# ATmega324PB_Xplained_Pro_EDBG.net
KiCad netlist of a schematic drawn in Altium Designer
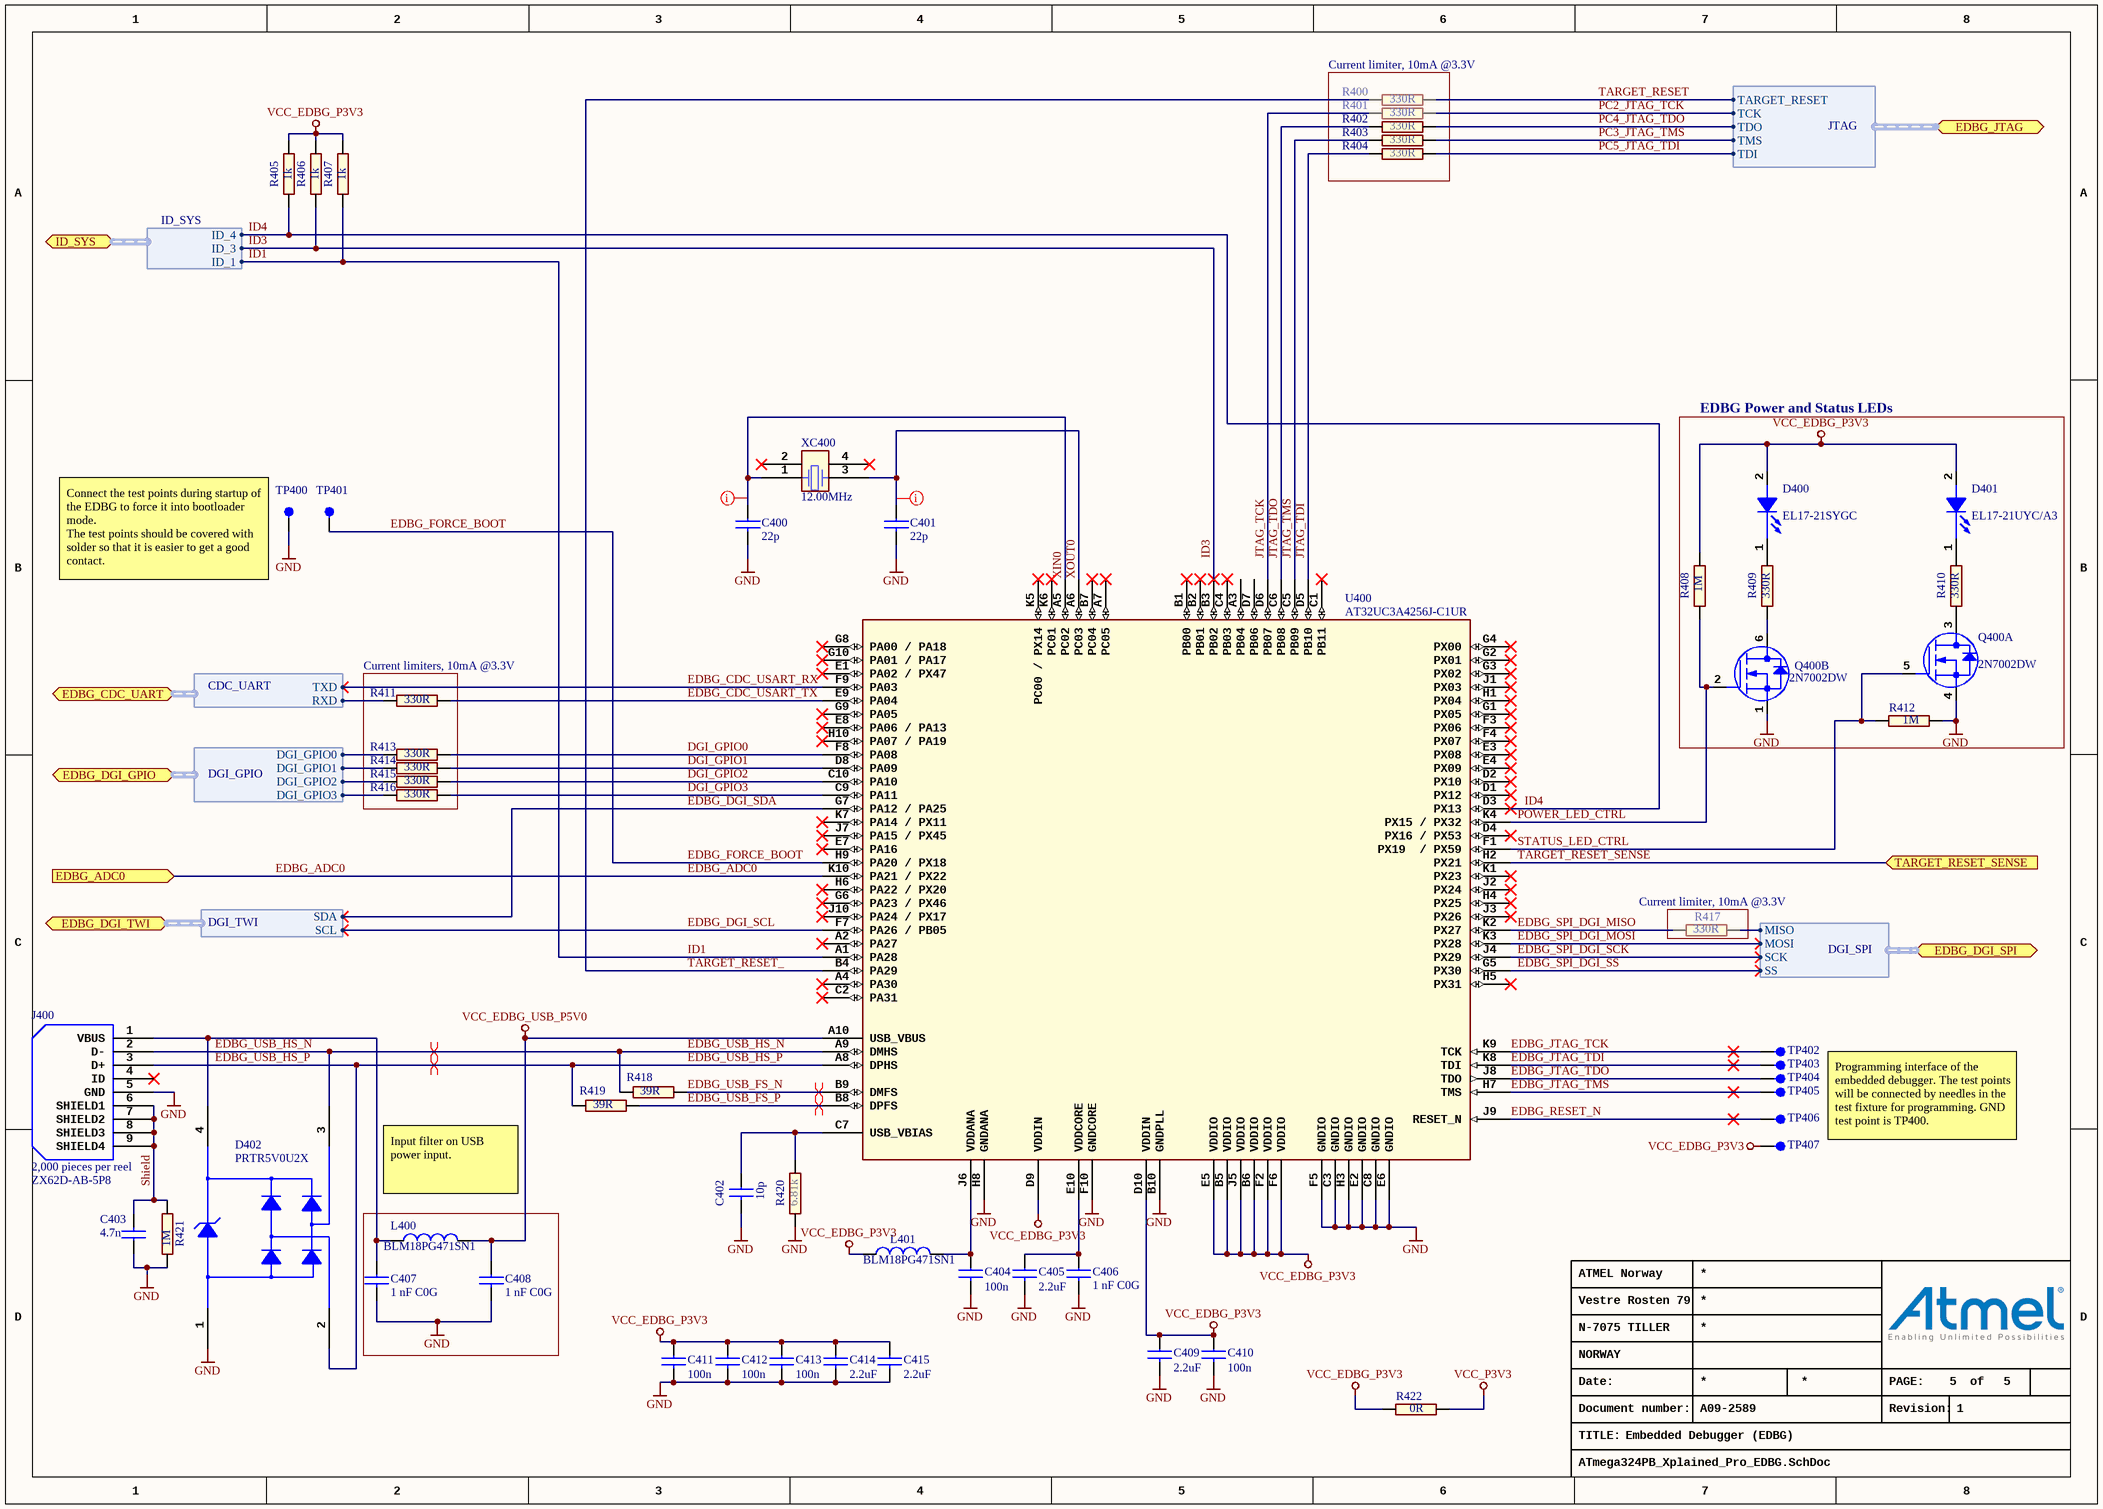
[diagram p0: ATmega324PB_Xplained_Pro_EDBG.SchDoc]

(export (version "E")
  (design (tool "Eeschema 10.0.6"))
  (components
    (comp (ref "C400")
      (value "22p")
      (footprint "AP1-00053")
      (description "Ceramic capacitor, SMD 0402, NP0, 50V, +/-5%")
      (fields (field (name "TOLERANCE") "50V, +/-5%"))
      (libsource (lib "AltiumDbLib") (part "CAP-NONPOL"))
    )
    (comp (ref "C401")
      (value "22p")
      (footprint "AP1-00053")
      (description "Ceramic capacitor, SMD 0402, NP0, 50V, +/-5%")
      (fields (field (name "TOLERANCE") "50V, +/-5%"))
      (libsource (lib "AltiumDbLib") (part "CAP-NONPOL"))
    )
    (comp (ref "C402")
      (value "10p")
      (footprint "AP1-00053")
      (description "Ceramic capacitor, SMD 0402, NP0, 50V, +/-5%")
      (fields (field (name "TOLERANCE") "50V, +/-5%"))
      (libsource (lib "AltiumDbLib") (part "CAP-NONPOL"))
    )
    (comp (ref "C403")
      (value "4.7n")
      (footprint "AP1-00053")
      (description "Ceramic capacitor, SMD 0402, X7R, 25V, +/-10%")
      (fields (field (name "TOLERANCE") "25V, +/-10%"))
      (libsource (lib "AltiumDbLib") (part "CAP-NONPOL"))
    )
    (comp (ref "C404")
      (value "100n")
      (footprint "AP1-00053")
      (description "Ceramic capacitor, SMD 0402, X7R, 16V, +/-10%")
      (fields (field (name "TOLERANCE") "16V, +/-10%") (field (name "MANUFACTURER") "Kemet"))
      (libsource (lib "AltiumDbLib") (part "CAP-NONPOL"))
    )
    (comp (ref "C405")
      (value "2.2uF")
      (footprint "AP1-00053")
      (description "Ceramic capacitor, SMD 0402, X5R, 6.3V, +/-20%")
      (fields (field (name "TOLERANCE") "Â±20%") (field (name "MANUFACTURER") "Kemet"))
      (libsource (lib "AltiumDbLib") (part "CAP-NONPOL"))
    )
    (comp (ref "C406")
      (value "1 nF C0G")
      (footprint "AP1-00053")
      (description "Ceramic capacitor, SMD 0402, C0G, 50V, +/-5%")
      (fields (field (name "TOLERANCE") "5%") (field (name "MANUFACTURER") "Murata"))
      (libsource (lib "AltiumDbLib") (part "CAP-NONPOL"))
    )
    (comp (ref "C407")
      (value "1 nF C0G")
      (footprint "AP1-00053")
      (description "Ceramic capacitor, SMD 0402, C0G, 50V, +/-5%")
      (fields (field (name "TOLERANCE") "5%") (field (name "MANUFACTURER") "Murata"))
      (libsource (lib "AltiumDbLib") (part "CAP-NONPOL"))
    )
    (comp (ref "C408")
      (value "1 nF C0G")
      (footprint "AP1-00053")
      (description "Ceramic capacitor, SMD 0402, C0G, 50V, +/-5%")
      (fields (field (name "TOLERANCE") "5%") (field (name "MANUFACTURER") "Murata"))
      (libsource (lib "AltiumDbLib") (part "CAP-NONPOL"))
    )
    (comp (ref "C409")
      (value "2.2uF")
      (footprint "AP1-00053")
      (description "Ceramic capacitor, SMD 0402, X5R, 6.3V, +/-20%")
      (fields (field (name "TOLERANCE") "Â±20%") (field (name "MANUFACTURER") "Kemet"))
      (libsource (lib "AltiumDbLib") (part "CAP-NONPOL"))
    )
    (comp (ref "C410")
      (value "100n")
      (footprint "AP1-00053")
      (description "Ceramic capacitor, SMD 0402, X7R, 16V, +/-10%")
      (fields (field (name "TOLERANCE") "16V, +/-10%") (field (name "MANUFACTURER") "Kemet"))
      (libsource (lib "AltiumDbLib") (part "CAP-NONPOL"))
    )
    (comp (ref "C411")
      (value "100n")
      (footprint "AP1-00053")
      (description "Ceramic capacitor, SMD 0402, X7R, 16V, +/-10%")
      (fields (field (name "TOLERANCE") "16V, +/-10%") (field (name "MANUFACTURER") "Kemet"))
      (libsource (lib "AltiumDbLib") (part "CAP-NONPOL"))
    )
    (comp (ref "C412")
      (value "100n")
      (footprint "AP1-00053")
      (description "Ceramic capacitor, SMD 0402, X7R, 16V, +/-10%")
      (fields (field (name "TOLERANCE") "16V, +/-10%") (field (name "MANUFACTURER") "Kemet"))
      (libsource (lib "AltiumDbLib") (part "CAP-NONPOL"))
    )
    (comp (ref "C413")
      (value "100n")
      (footprint "AP1-00053")
      (description "Ceramic capacitor, SMD 0402, X7R, 16V, +/-10%")
      (fields (field (name "TOLERANCE") "16V, +/-10%") (field (name "MANUFACTURER") "Kemet"))
      (libsource (lib "AltiumDbLib") (part "CAP-NONPOL"))
    )
    (comp (ref "C414")
      (value "2.2uF")
      (footprint "AP1-00053")
      (description "Ceramic capacitor, SMD 0402, X5R, 6.3V, +/-20%")
      (fields (field (name "TOLERANCE") "Â±20%") (field (name "MANUFACTURER") "Kemet"))
      (libsource (lib "AltiumDbLib") (part "CAP-NONPOL"))
    )
    (comp (ref "C415")
      (value "2.2uF")
      (footprint "AP1-00053")
      (description "Ceramic capacitor, SMD 0402, X5R, 6.3V, +/-20%")
      (fields (field (name "TOLERANCE") "Â±20%") (field (name "MANUFACTURER") "Kemet"))
      (libsource (lib "AltiumDbLib") (part "CAP-NONPOL"))
    )
    (comp (ref "D400")
      (value "EL17-21SYGC")
      (footprint "AP4-00013")
      (description "LED, Green, Wave length=575nm, SMD 0805, ±70°")
      (fields (field (name "MANUFACTURER") "Everlight"))
      (libsource (lib "AltiumDbLib") (part "LED_12"))
    )
    (comp (ref "D401")
      (value "EL17-21UYC/A3")
      (footprint "AP4-00013")
      (description "LED, Yellow, Wave length=591nm, SMD 0805, ±70°")
      (fields (field (name "MANUFACTURER") "Everlight") (field (name "MPN") "17-21UYC/S530-A3/TR8"))
      (libsource (lib "AltiumDbLib") (part "LED_12"))
    )
    (comp (ref "D402")
      (value "PRTR5V0U2X")
      (footprint "AP4-00001")
      (description "Double rail-to-rail USB ESD protection diode")
      (fields
        (field (name "MANUFACTURER") "NXP")
        (field (name "Comment") "Changed manufacturer from Philips to NXP.")
      )
      (libsource (lib "AltiumDbLib") (part "PRTR5V0U2X"))
    )
    (comp (ref "J400")
      (value "2,000 pieces per reel")
      (footprint "AP8-00852")
      (description "Micro USB AB Connector, Standard SMT + DIP")
      (fields
        (field (name "ALTIUM_VALUE") "ZX62D-AB-5P8")
        (field (name "MANUFACTURER") "HIROSE")
        (field (name "MPN") "ZX62D-AB-5P8")
      )
      (libsource (lib "AltiumDbLib") (part "USB_AB"))
    )
    (comp (ref "L400")
      (value "BLM18PG471SN1")
      (footprint "AP3-00005")
      (description "SMD RF inductor 0603. Z=470Ohm (@100MHz), Max R(dc)=0.65Ohm, Max current=1A")
      (fields (field (name "TOLERANCE") "±25%") (field (name "MANUFACTURER") "Murata"))
      (libsource (lib "AltiumDbLib") (part "INDUCTOR"))
    )
    (comp (ref "L401")
      (value "BLM18PG471SN1")
      (footprint "AP3-00005")
      (description "SMD RF inductor 0603. Z=470Ohm (@100MHz), Max R(dc)=0.65Ohm, Max current=1A")
      (fields (field (name "TOLERANCE") "±25%") (field (name "MANUFACTURER") "Murata"))
      (libsource (lib "AltiumDbLib") (part "INDUCTOR"))
    )
    (comp (ref "Q400")
      (value "2N7002DW")
      (footprint "AP5-00001")
      (description "Dual N-Channel MOSFET, 60V, 115mA cont,RDS(ON) < 7.5 Ohm @50mA@5V, SOT-363")
      (fields
        (field (name "MANUFACTURER") "Fairchild")
        (field (name "Comment") "Same as 2N7002 but with two MOSFETs in one package")
      )
      (libsource (lib "AltiumDbLib") (part "MOSFET_DUAL_N_S2G2D1S1G1D2"))
    )
    (comp (ref "R400")
      (value "330R")
      (footprint "AP2-00000")
      (description "Thick film resistor, SMD 0402, 1/16W, 1%")
      (fields (field (name "TOLERANCE") "1 %"))
      (libsource (lib "") (part "R2_1"))
    )
    (comp (ref "R401")
      (value "330R")
      (footprint "AP2-00000")
      (description "Thick film resistor, SMD 0402, 1/16W, 1%")
      (fields (field (name "TOLERANCE") "1 %"))
      (libsource (lib "") (part "R2_1"))
    )
    (comp (ref "R402")
      (value "330R")
      (footprint "AP2-00000")
      (description "Thick film resistor, SMD 0402, 1/16W, 1%")
      (fields (field (name "TOLERANCE") "1 %"))
      (libsource (lib "") (part "R2_1"))
    )
    (comp (ref "R403")
      (value "330R")
      (footprint "AP2-00000")
      (description "Thick film resistor, SMD 0402, 1/16W, 1%")
      (fields (field (name "TOLERANCE") "1 %"))
      (libsource (lib "") (part "R2_1"))
    )
    (comp (ref "R404")
      (value "330R")
      (footprint "AP2-00000")
      (description "Thick film resistor, SMD 0402, 1/16W, 1%")
      (fields (field (name "TOLERANCE") "1 %"))
      (libsource (lib "") (part "R2_1"))
    )
    (comp (ref "R405")
      (value "1k")
      (footprint "AP2-00000")
      (description "Thick film resistor, SMD 0402, 1/16W, 1%")
      (fields (field (name "TOLERANCE") "1 %"))
      (libsource (lib "AltiumDbLib") (part "R2"))
    )
    (comp (ref "R406")
      (value "1k")
      (footprint "AP2-00000")
      (description "Thick film resistor, SMD 0402, 1/16W, 1%")
      (fields (field (name "TOLERANCE") "1 %"))
      (libsource (lib "AltiumDbLib") (part "R2"))
    )
    (comp (ref "R407")
      (value "1k")
      (footprint "AP2-00000")
      (description "Thick film resistor, SMD 0402, 1/16W, 1%")
      (fields (field (name "TOLERANCE") "1 %"))
      (libsource (lib "AltiumDbLib") (part "R2"))
    )
    (comp (ref "R408")
      (value "1M")
      (footprint "AP2-00000")
      (description "Thick film resistor, SMD 0402, 1/16W, 1%")
      (fields (field (name "TOLERANCE") "1 %"))
      (libsource (lib "AltiumDbLib") (part "R2"))
    )
    (comp (ref "R409")
      (value "330R")
      (footprint "AP2-00000")
      (description "Thick film resistor, SMD 0402, 1/16W, 1%")
      (fields (field (name "TOLERANCE") "1 %"))
      (libsource (lib "AltiumDbLib") (part "R2"))
    )
    (comp (ref "R410")
      (value "330R")
      (footprint "AP2-00000")
      (description "Thick film resistor, SMD 0402, 1/16W, 1%")
      (fields (field (name "TOLERANCE") "1 %"))
      (libsource (lib "AltiumDbLib") (part "R2"))
    )
    (comp (ref "R411")
      (value "330R")
      (footprint "AP2-00000")
      (description "Thick film resistor, SMD 0402, 1/16W, 1%")
      (fields (field (name "TOLERANCE") "1 %"))
      (libsource (lib "") (part "R2_1"))
    )
    (comp (ref "R412")
      (value "1M")
      (footprint "AP2-00000")
      (description "Thick film resistor, SMD 0402, 1/16W, 1%")
      (fields (field (name "TOLERANCE") "1 %"))
      (libsource (lib "") (part "R2_4"))
    )
    (comp (ref "R413")
      (value "330R")
      (footprint "AP2-00000")
      (description "Thick film resistor, SMD 0402, 1/16W, 1%")
      (fields (field (name "TOLERANCE") "1 %"))
      (libsource (lib "") (part "R2_1"))
    )
    (comp (ref "R414")
      (value "330R")
      (footprint "AP2-00000")
      (description "Thick film resistor, SMD 0402, 1/16W, 1%")
      (fields (field (name "TOLERANCE") "1 %"))
      (libsource (lib "") (part "R2_1"))
    )
    (comp (ref "R415")
      (value "330R")
      (footprint "AP2-00000")
      (description "Thick film resistor, SMD 0402, 1/16W, 1%")
      (fields (field (name "TOLERANCE") "1 %"))
      (libsource (lib "") (part "R2_1"))
    )
    (comp (ref "R416")
      (value "330R")
      (footprint "AP2-00000")
      (description "Thick film resistor, SMD 0402, 1/16W, 1%")
      (fields (field (name "TOLERANCE") "1 %"))
      (libsource (lib "") (part "R2_1"))
    )
    (comp (ref "R417")
      (value "330R")
      (footprint "AP2-00000")
      (description "Thick film resistor, SMD 0402, 1/16W, 1%")
      (fields (field (name "TOLERANCE") "1 %"))
      (libsource (lib "") (part "R2_1"))
    )
    (comp (ref "R418")
      (value "39R")
      (footprint "AP2-00011")
      (description "Thick film resistor, SMD 0402, 1/16W, 1%")
      (fields (field (name "TOLERANCE") "1 %"))
      (libsource (lib "") (part "R2_2"))
    )
    (comp (ref "R419")
      (value "39R")
      (footprint "AP2-00011")
      (description "Thick film resistor, SMD 0402, 1/16W, 1%")
      (fields (field (name "TOLERANCE") "1 %"))
      (libsource (lib "") (part "R2_2"))
    )
    (comp (ref "R420")
      (value "6.81k")
      (footprint "AP2-00011")
      (description "Thick film resistor, SMD 0402, 1/16W, 1%")
      (fields (field (name "TOLERANCE") "1%"))
      (libsource (lib "AltiumDbLib") (part "R2"))
    )
    (comp (ref "R421")
      (value "1M")
      (footprint "AP2-00011")
      (description "Thick film resistor, SMD 0402, 1/16W, 1%")
      (fields (field (name "TOLERANCE") "1 %"))
      (libsource (lib "") (part "R2_3"))
    )
    (comp (ref "R422")
      (value "0R")
      (footprint "AP2-00000")
      (description "Thick film resistor, SMD 0402, 1/16W, 1%")
      (fields (field (name "TOLERANCE") "1 %") (field (name "MANUFACTURER") "(n/a)"))
      (libsource (lib "") (part "R2_1"))
    )
    (comp (ref "TP400")
      (value "~")
      (footprint "AP8-00010")
      (description "Single SMD testpad")
      (libsource (lib "AltiumDbLib") (part "TESTPOINT"))
    )
    (comp (ref "TP401")
      (value "~")
      (footprint "AP8-00010")
      (description "Single SMD testpad")
      (libsource (lib "AltiumDbLib") (part "TESTPOINT"))
    )
    (comp (ref "TP402")
      (value "~")
      (footprint "AP8-00010")
      (description "Single SMD testpad")
      (libsource (lib "AltiumDbLib") (part "TESTPOINT"))
    )
    (comp (ref "TP403")
      (value "~")
      (footprint "AP8-00010")
      (description "Single SMD testpad")
      (libsource (lib "AltiumDbLib") (part "TESTPOINT"))
    )
    (comp (ref "TP404")
      (value "~")
      (footprint "AP8-00010")
      (description "Single SMD testpad")
      (libsource (lib "AltiumDbLib") (part "TESTPOINT"))
    )
    (comp (ref "TP405")
      (value "~")
      (footprint "AP8-00010")
      (description "Single SMD testpad")
      (libsource (lib "AltiumDbLib") (part "TESTPOINT"))
    )
    (comp (ref "TP406")
      (value "~")
      (footprint "AP8-00010")
      (description "Single SMD testpad")
      (libsource (lib "AltiumDbLib") (part "TESTPOINT"))
    )
    (comp (ref "TP407")
      (value "~")
      (footprint "AP8-00010")
      (description "Single SMD testpad")
      (libsource (lib "AltiumDbLib") (part "TESTPOINT"))
    )
    (comp (ref "U400")
      (value "AT32UC3A4256J-C1UR")
      (footprint "AP6-00206")
      (description "AVR 32-bit RISC MCU")
      (fields (field (name "MANUFACTURER") "ATMEL") (field (name "Comment") "100 ball VFBGA"))
      (libsource (lib "AltiumDbLib") (part "AT32UC3A4_VFBGA"))
    )
    (comp (ref "XC400")
      (value "12.00MHz")
      (footprint "AP7-00039")
      (description "Fox FQ5032B 12.0MHz SMD crystal 738B-12")
      (fields (field (name "TOLERANCE") "Â±30ppm") (field (name "MANUFACTURER") "Fox  Electronics"))
      (libsource (lib "AltiumDbLib") (part "CRYSTAL1324"))
    )
  )
  (nets
    (net (code "7") (name "/DGI_GPIO0") (class "Default")
      (node (ref "R413") (pin "2") (pinfunction "2_2") (pintype "passive"))
      (node (ref "U400") (pin "F8") (pinfunction "PA08_F8") (pintype "bidirectional"))
    )
    (net (code "8") (name "/DGI_GPIO1") (class "Default")
      (node (ref "R414") (pin "2") (pinfunction "2_2") (pintype "passive"))
      (node (ref "U400") (pin "D8") (pinfunction "PA09_D8") (pintype "bidirectional"))
    )
    (net (code "9") (name "/DGI_GPIO2") (class "Default")
      (node (ref "R415") (pin "2") (pinfunction "2_2") (pintype "passive"))
      (node (ref "U400") (pin "C10") (pinfunction "PA10_C10") (pintype "bidirectional"))
    )
    (net (code "10") (name "/DGI_GPIO3") (class "Default")
      (node (ref "R416") (pin "2") (pinfunction "2_2") (pintype "passive"))
      (node (ref "U400") (pin "C9") (pinfunction "PA11_C9") (pintype "bidirectional"))
    )
    (net (code "11") (name "/EDBG_ADC0") (class "Default")
      (node (ref "U400") (pin "K10") (pinfunction "PA21_/_PX22_K10") (pintype "bidirectional"))
    )
    (net (code "12") (name "/EDBG_CDC_USART_RX") (class "Default")
      (node (ref "U400") (pin "F9") (pinfunction "PA03_F9") (pintype "bidirectional+no_connect"))
    )
    (net (code "13") (name "/EDBG_CDC_USART_TX") (class "Default")
      (node (ref "R411") (pin "2") (pinfunction "2_2") (pintype "passive"))
      (node (ref "U400") (pin "E9") (pinfunction "PA04_E9") (pintype "bidirectional"))
    )
    (net (code "14") (name "/EDBG_DGI_SCL") (class "Default")
      (node (ref "U400") (pin "F7") (pinfunction "PA26_/_PB05_F7") (pintype "bidirectional+no_connect"))
    )
    (net (code "15") (name "/EDBG_DGI_SDA") (class "Default")
      (node (ref "U400") (pin "G7") (pinfunction "PA12_/_PA25_G7") (pintype "bidirectional+no_connect"))
    )
    (net (code "16") (name "/EDBG_FORCE_BOOT") (class "Default")
      (node (ref "TP401") (pin "1") (pinfunction "1_1") (pintype "passive"))
      (node (ref "U400") (pin "H9") (pinfunction "PA20_/_PX18_H9") (pintype "bidirectional"))
    )
    (net (code "17") (name "/EDBG_JTAG_TCK") (class "Default")
      (node (ref "TP402") (pin "1") (pinfunction "1_1") (pintype "passive"))
      (node (ref "U400") (pin "K9") (pinfunction "TCK_K9") (pintype "input"))
    )
    (net (code "18") (name "/EDBG_JTAG_TDI") (class "Default")
      (node (ref "TP403") (pin "1") (pinfunction "1_1") (pintype "passive"))
      (node (ref "U400") (pin "K8") (pinfunction "TDI_K8") (pintype "input"))
    )
    (net (code "19") (name "/EDBG_JTAG_TDO") (class "Default")
      (node (ref "TP404") (pin "1") (pinfunction "1_1") (pintype "passive"))
      (node (ref "U400") (pin "J8") (pinfunction "TDO_J8") (pintype "output"))
    )
    (net (code "20") (name "/EDBG_JTAG_TMS") (class "Default")
      (node (ref "TP405") (pin "1") (pinfunction "1_1") (pintype "passive"))
      (node (ref "U400") (pin "H7") (pinfunction "TMS_H7") (pintype "input"))
    )
    (net (code "21") (name "/EDBG_RESET_N") (class "Default")
      (node (ref "TP406") (pin "1") (pinfunction "1_1") (pintype "passive"))
      (node (ref "U400") (pin "J9") (pinfunction "RESET_N_J9") (pintype "input"))
    )
    (net (code "22") (name "/EDBG_SPI_DGI_MISO") (class "Default")
      (node (ref "R417") (pin "1") (pinfunction "1_1") (pintype "passive"))
      (node (ref "U400") (pin "K2") (pinfunction "PX27_K2") (pintype "bidirectional"))
    )
    (net (code "23") (name "/EDBG_SPI_DGI_MOSI") (class "Default")
      (node (ref "U400") (pin "K3") (pinfunction "PX28_K3") (pintype "bidirectional+no_connect"))
    )
    (net (code "24") (name "/EDBG_SPI_DGI_SCK") (class "Default")
      (node (ref "U400") (pin "J4") (pinfunction "PX29_J4") (pintype "bidirectional+no_connect"))
    )
    (net (code "25") (name "/EDBG_SPI_DGI_SS") (class "Default")
      (node (ref "U400") (pin "G5") (pinfunction "PX30_G5") (pintype "bidirectional+no_connect"))
    )
    (net (code "26") (name "/EDBG_USB_FS_N") (class "Default")
      (node (ref "R418") (pin "2") (pinfunction "2_2") (pintype "passive"))
      (node (ref "U400") (pin "B9") (pinfunction "DMFS_B9") (pintype "bidirectional"))
    )
    (net (code "27") (name "/EDBG_USB_FS_P") (class "Default")
      (node (ref "R419") (pin "2") (pinfunction "2_2") (pintype "passive"))
      (node (ref "U400") (pin "B8") (pinfunction "DPFS_B8") (pintype "bidirectional"))
    )
    (net (code "28") (name "/EDBG_USB_HS_N") (class "Default")
      (node (ref "D402") (pin "3") (pinfunction "I/O_2_3") (pintype "passive"))
      (node (ref "J400") (pin "2") (pinfunction "D-_2") (pintype "passive"))
      (node (ref "R418") (pin "1") (pinfunction "1_1") (pintype "passive"))
      (node (ref "U400") (pin "A9") (pinfunction "DMHS_A9") (pintype "bidirectional"))
    )
    (net (code "29") (name "/EDBG_USB_HS_P") (class "Default")
      (node (ref "D402") (pin "2") (pinfunction "I/O_1_2") (pintype "passive"))
      (node (ref "J400") (pin "3") (pinfunction "D+_3") (pintype "passive"))
      (node (ref "R419") (pin "1") (pinfunction "1_1") (pintype "passive"))
      (node (ref "U400") (pin "A8") (pinfunction "DPHS_A8") (pintype "bidirectional"))
    )
    (net (code "30") (name "/ID1") (class "Default")
      (node (ref "R407") (pin "1") (pinfunction "1_1") (pintype "passive"))
      (node (ref "U400") (pin "A1") (pinfunction "PA28_A1") (pintype "bidirectional"))
    )
    (net (code "31") (name "/ID3") (class "Default")
      (node (ref "R406") (pin "1") (pinfunction "1_1") (pintype "passive"))
      (node (ref "U400") (pin "B3") (pinfunction "PB02_B3") (pintype "bidirectional"))
    )
    (net (code "32") (name "/ID4") (class "Default")
      (node (ref "R405") (pin "1") (pinfunction "1_1") (pintype "passive"))
      (node (ref "U400") (pin "D3") (pinfunction "PX13_D3") (pintype "bidirectional"))
    )
    (net (code "33") (name "/JTAG_TCK") (class "Default")
      (node (ref "R401") (pin "1") (pinfunction "1_1") (pintype "passive"))
      (node (ref "U400") (pin "D6") (pinfunction "PB07_D6") (pintype "bidirectional"))
    )
    (net (code "34") (name "/JTAG_TDI") (class "Default")
      (node (ref "R404") (pin "1") (pinfunction "1_1") (pintype "passive"))
      (node (ref "U400") (pin "D5") (pinfunction "PB10_D5") (pintype "bidirectional"))
    )
    (net (code "35") (name "/JTAG_TDO") (class "Default")
      (node (ref "R402") (pin "1") (pinfunction "1_1") (pintype "passive"))
      (node (ref "U400") (pin "C6") (pinfunction "PB08_C6") (pintype "bidirectional"))
    )
    (net (code "36") (name "/JTAG_TMS") (class "Default")
      (node (ref "R403") (pin "1") (pinfunction "1_1") (pintype "passive"))
      (node (ref "U400") (pin "C5") (pinfunction "PB09_C5") (pintype "bidirectional"))
    )
    (net (code "37") (name "/MISO") (class "Default")
      (node (ref "R417") (pin "2") (pinfunction "2_2") (pintype "passive"))
    )
    (net (code "38") (name "/PC2_JTAG_TCK") (class "Default")
      (node (ref "R401") (pin "2") (pinfunction "2_2") (pintype "passive"))
    )
    (net (code "39") (name "/PC3_JTAG_TMS") (class "Default")
      (node (ref "R403") (pin "2") (pinfunction "2_2") (pintype "passive"))
    )
    (net (code "40") (name "/PC4_JTAG_TDO") (class "Default")
      (node (ref "R402") (pin "2") (pinfunction "2_2") (pintype "passive"))
    )
    (net (code "41") (name "/PC5_JTAG_TDI") (class "Default")
      (node (ref "R404") (pin "2") (pinfunction "2_2") (pintype "passive"))
    )
    (net (code "42") (name "/POWER_LED_CTRL") (class "Default")
      (node (ref "Q400") (pin "2") (pinfunction "G2_2") (pintype "passive"))
      (node (ref "R408") (pin "1") (pinfunction "1_1") (pintype "passive"))
      (node (ref "U400") (pin "K4") (pinfunction "PX15_/_PX32_K4") (pintype "bidirectional"))
    )
    (net (code "43") (name "/RXD") (class "Default")
      (node (ref "R411") (pin "1") (pinfunction "1_1") (pintype "passive"))
    )
    (net (code "44") (name "/STATUS_LED_CTRL") (class "Default")
      (node (ref "Q400") (pin "5") (pinfunction "G1_5") (pintype "passive"))
      (node (ref "R412") (pin "2") (pinfunction "2_2") (pintype "passive"))
      (node (ref "U400") (pin "F1") (pinfunction "PX19__/_PX59_F1") (pintype "bidirectional"))
    )
    (net (code "45") (name "/Shield") (class "Default")
      (node (ref "C403") (pin "2") (pinfunction "2_2") (pintype "passive"))
      (node (ref "J400") (pin "6") (pinfunction "SHIELD1_6") (pintype "passive"))
      (node (ref "J400") (pin "7") (pinfunction "SHIELD2_7") (pintype "passive"))
      (node (ref "J400") (pin "8") (pinfunction "SHIELD3_8") (pintype "passive"))
      (node (ref "J400") (pin "9") (pinfunction "SHIELD4_9") (pintype "passive"))
      (node (ref "R421") (pin "2") (pinfunction "2_2") (pintype "passive"))
    )
    (net (code "46") (name "/TARGET_RESET") (class "Default")
      (node (ref "R400") (pin "2") (pinfunction "2_2") (pintype "passive"))
    )
    (net (code "47") (name "/TARGET_RESET_") (class "Default")
      (node (ref "R400") (pin "1") (pinfunction "1_1") (pintype "passive"))
      (node (ref "U400") (pin "B4") (pinfunction "PA29_B4") (pintype "bidirectional"))
    )
    (net (code "48") (name "/TARGET_RESET_SENSE") (class "Default")
      (node (ref "U400") (pin "H2") (pinfunction "PX21_H2") (pintype "bidirectional"))
    )
    (net (code "49") (name "/XIN0") (class "Default")
      (node (ref "C400") (pin "1") (pinfunction "1_1") (pintype "passive"))
      (node (ref "U400") (pin "A5") (pinfunction "PC02_A5") (pintype "bidirectional"))
      (node (ref "XC400") (pin "1") (pinfunction "1_1") (pintype "passive"))
    )
    (net (code "50") (name "/XOUT0") (class "Default")
      (node (ref "C401") (pin "1") (pinfunction "1_1") (pintype "passive"))
      (node (ref "U400") (pin "A6") (pinfunction "PC03_A6") (pintype "bidirectional"))
      (node (ref "XC400") (pin "3") (pinfunction "3_3") (pintype "passive"))
    )
    (net (code "57") (name "GND") (class "Default")
      (node (ref "C400") (pin "2") (pinfunction "2_2") (pintype "passive"))
      (node (ref "C401") (pin "2") (pinfunction "2_2") (pintype "passive"))
      (node (ref "C402") (pin "2") (pinfunction "2_2") (pintype "passive"))
      (node (ref "C403") (pin "1") (pinfunction "1_1") (pintype "passive"))
      (node (ref "C404") (pin "2") (pinfunction "2_2") (pintype "passive"))
      (node (ref "C405") (pin "2") (pinfunction "2_2") (pintype "passive"))
      (node (ref "C406") (pin "2") (pinfunction "2_2") (pintype "passive"))
      (node (ref "C407") (pin "2") (pinfunction "2_2") (pintype "passive"))
      (node (ref "C408") (pin "2") (pinfunction "2_2") (pintype "passive"))
      (node (ref "C409") (pin "2") (pinfunction "2_2") (pintype "passive"))
      (node (ref "C410") (pin "2") (pinfunction "2_2") (pintype "passive"))
      (node (ref "C411") (pin "2") (pinfunction "2_2") (pintype "passive"))
      (node (ref "C412") (pin "2") (pinfunction "2_2") (pintype "passive"))
      (node (ref "C413") (pin "2") (pinfunction "2_2") (pintype "passive"))
      (node (ref "C414") (pin "2") (pinfunction "2_2") (pintype "passive"))
      (node (ref "C415") (pin "2") (pinfunction "2_2") (pintype "passive"))
      (node (ref "D402") (pin "1") (pinfunction "GND_1") (pintype "passive"))
      (node (ref "J400") (pin "5") (pinfunction "GND_5") (pintype "passive"))
      (node (ref "Q400") (pin "1") (pinfunction "S2_1") (pintype "passive"))
      (node (ref "Q400") (pin "4") (pinfunction "S1_4") (pintype "passive"))
      (node (ref "R412") (pin "1") (pinfunction "1_1") (pintype "passive"))
      (node (ref "R420") (pin "1") (pinfunction "1_1") (pintype "passive"))
      (node (ref "R421") (pin "1") (pinfunction "1_1") (pintype "passive"))
      (node (ref "TP400") (pin "1") (pinfunction "1_1") (pintype "passive"))
      (node (ref "U400") (pin "B10") (pinfunction "GNDPLL_B10") (pintype "power_in"))
      (node (ref "U400") (pin "C3") (pinfunction "GNDIO_C3") (pintype "power_in"))
      (node (ref "U400") (pin "C8") (pinfunction "GNDIO_C8") (pintype "power_in"))
      (node (ref "U400") (pin "E2") (pinfunction "GNDIO_E2") (pintype "power_in"))
      (node (ref "U400") (pin "E6") (pinfunction "GNDIO_E6") (pintype "power_in"))
      (node (ref "U400") (pin "F10") (pinfunction "GNDCORE_F10") (pintype "power_in"))
      (node (ref "U400") (pin "F5") (pinfunction "GNDIO_F5") (pintype "power_in"))
      (node (ref "U400") (pin "H3") (pinfunction "GNDIO_H3") (pintype "power_in"))
      (node (ref "U400") (pin "H8") (pinfunction "GNDANA_H8") (pintype "power_in"))
    )
    (net (code "58") (name "Net-(D400-CATHODE)") (class "Default")
      (node (ref "D400") (pin "1") (pinfunction "CATHODE_1") (pintype "passive"))
      (node (ref "R409") (pin "2") (pinfunction "2_2") (pintype "passive"))
    )
    (net (code "59") (name "Net-(D401-CATHODE)") (class "Default")
      (node (ref "D401") (pin "1") (pinfunction "CATHODE_1") (pintype "passive"))
      (node (ref "R410") (pin "2") (pinfunction "2_2") (pintype "passive"))
    )
    (net (code "60") (name "Net-(D402-VCC)") (class "Default")
      (node (ref "C407") (pin "1") (pinfunction "1_1") (pintype "passive"))
      (node (ref "D402") (pin "4") (pinfunction "VCC_4") (pintype "passive"))
      (node (ref "J400") (pin "1") (pinfunction "VBUS_1") (pintype "passive"))
      (node (ref "L400") (pin "1") (pinfunction "1_1") (pintype "passive"))
    )
    (net (code "61") (name "Net-(Q400A-D1)") (class "Default")
      (node (ref "Q400") (pin "3") (pinfunction "D1_3") (pintype "passive"))
      (node (ref "R410") (pin "1") (pinfunction "1_1") (pintype "passive"))
    )
    (net (code "62") (name "Net-(Q400B-D2)") (class "Default")
      (node (ref "Q400") (pin "6") (pinfunction "D2_6") (pintype "passive"))
      (node (ref "R409") (pin "1") (pinfunction "1_1") (pintype "passive"))
    )
    (net (code "63") (name "Net-(U400-USB_VBIAS)") (class "Default")
      (node (ref "C402") (pin "1") (pinfunction "1_1") (pintype "passive"))
      (node (ref "R420") (pin "2") (pinfunction "2_2") (pintype "passive"))
      (node (ref "U400") (pin "C7") (pinfunction "USB_VBIAS_C7") (pintype "power_in"))
    )
    (net (code "64") (name "Net-(U400-VDDANA)") (class "Default")
      (node (ref "C404") (pin "1") (pinfunction "1_1") (pintype "passive"))
      (node (ref "L401") (pin "2") (pinfunction "2_2") (pintype "passive"))
      (node (ref "U400") (pin "J6") (pinfunction "VDDANA_J6") (pintype "power_in"))
    )
    (net (code "65") (name "Net-(U400-VDDCORE)") (class "Default")
      (node (ref "C405") (pin "1") (pinfunction "1_1") (pintype "passive"))
      (node (ref "C406") (pin "1") (pinfunction "1_1") (pintype "passive"))
      (node (ref "U400") (pin "E10") (pinfunction "VDDCORE_E10") (pintype "power_in"))
    )
    (net (code "66") (name "VCC_EDBG_P3V3") (class "Default")
      (node (ref "C409") (pin "1") (pinfunction "1_1") (pintype "passive"))
      (node (ref "C410") (pin "1") (pinfunction "1_1") (pintype "passive"))
      (node (ref "C411") (pin "1") (pinfunction "1_1") (pintype "passive"))
      (node (ref "C412") (pin "1") (pinfunction "1_1") (pintype "passive"))
      (node (ref "C413") (pin "1") (pinfunction "1_1") (pintype "passive"))
      (node (ref "C414") (pin "1") (pinfunction "1_1") (pintype "passive"))
      (node (ref "C415") (pin "1") (pinfunction "1_1") (pintype "passive"))
      (node (ref "D400") (pin "2") (pinfunction "ANODE_2") (pintype "passive"))
      (node (ref "D401") (pin "2") (pinfunction "ANODE_2") (pintype "passive"))
      (node (ref "L401") (pin "1") (pinfunction "1_1") (pintype "passive"))
      (node (ref "R405") (pin "2") (pinfunction "2_2") (pintype "passive"))
      (node (ref "R406") (pin "2") (pinfunction "2_2") (pintype "passive"))
      (node (ref "R407") (pin "2") (pinfunction "2_2") (pintype "passive"))
      (node (ref "R408") (pin "2") (pinfunction "2_2") (pintype "passive"))
      (node (ref "R422") (pin "1") (pinfunction "1_1") (pintype "passive"))
      (node (ref "TP407") (pin "1") (pinfunction "1_1") (pintype "passive"))
      (node (ref "U400") (pin "B5") (pinfunction "VDDIO_B5") (pintype "power_in"))
      (node (ref "U400") (pin "B6") (pinfunction "VDDIO_B6") (pintype "power_in"))
      (node (ref "U400") (pin "D10") (pinfunction "VDDIN_D10") (pintype "power_in"))
      (node (ref "U400") (pin "D9") (pinfunction "VDDIN_D9") (pintype "power_in"))
      (node (ref "U400") (pin "E5") (pinfunction "VDDIO_E5") (pintype "power_in"))
      (node (ref "U400") (pin "F2") (pinfunction "VDDIO_F2") (pintype "power_in"))
      (node (ref "U400") (pin "F6") (pinfunction "VDDIO_F6") (pintype "power_in"))
      (node (ref "U400") (pin "J5") (pinfunction "VDDIO_J5") (pintype "power_in"))
    )
    (net (code "67") (name "VCC_EDBG_USB_P5V0") (class "Default")
      (node (ref "C408") (pin "1") (pinfunction "1_1") (pintype "passive"))
      (node (ref "L400") (pin "2") (pinfunction "2_2") (pintype "passive"))
      (node (ref "U400") (pin "A10") (pinfunction "USB_VBUS_A10") (pintype "power_in"))
    )
    (net (code "68") (name "VCC_P3V3") (class "Default")
      (node (ref "R422") (pin "2") (pinfunction "2_2") (pintype "passive"))
    )
    (net (code "69") (name "unconnected-(J400-ID-Pad4)") (class "Default")
      (node (ref "J400") (pin "4") (pinfunction "ID_4") (pintype "passive+no_connect"))
    )
    (net (code "70") (name "unconnected-(R413-Pad1)") (class "Default")
      (node (ref "R413") (pin "1") (pinfunction "1_1") (pintype "passive"))
    )
    (net (code "71") (name "unconnected-(R414-Pad1)") (class "Default")
      (node (ref "R414") (pin "1") (pinfunction "1_1") (pintype "passive"))
    )
    (net (code "72") (name "unconnected-(R415-Pad1)") (class "Default")
      (node (ref "R415") (pin "1") (pinfunction "1_1") (pintype "passive"))
    )
    (net (code "73") (name "unconnected-(R416-Pad1)") (class "Default")
      (node (ref "R416") (pin "1") (pinfunction "1_1") (pintype "passive"))
    )
    (net (code "74") (name "unconnected-(U400-PA00_{slash}_PA18-PadG8)") (class "Default")
      (node (ref "U400") (pin "G8") (pinfunction "PA00_/_PA18_G8") (pintype "bidirectional+no_connect"))
    )
    (net (code "75") (name "unconnected-(U400-PA01_{slash}_PA17-PadG10)") (class "Default")
      (node (ref "U400") (pin "G10") (pinfunction "PA01_/_PA17_G10") (pintype "bidirectional+no_connect"))
    )
    (net (code "76") (name "unconnected-(U400-PA02_{slash}_PX47-PadE1)") (class "Default")
      (node (ref "U400") (pin "E1") (pinfunction "PA02_/_PX47_E1") (pintype "bidirectional+no_connect"))
    )
    (net (code "77") (name "unconnected-(U400-PA05-PadG9)") (class "Default")
      (node (ref "U400") (pin "G9") (pinfunction "PA05_G9") (pintype "bidirectional+no_connect"))
    )
    (net (code "78") (name "unconnected-(U400-PA06_{slash}_PA13-PadE8)") (class "Default")
      (node (ref "U400") (pin "E8") (pinfunction "PA06_/_PA13_E8") (pintype "bidirectional+no_connect"))
    )
    (net (code "79") (name "unconnected-(U400-PA07_{slash}_PA19-PadH10)") (class "Default")
      (node (ref "U400") (pin "H10") (pinfunction "PA07_/_PA19_H10") (pintype "bidirectional+no_connect"))
    )
    (net (code "80") (name "unconnected-(U400-PA14_{slash}_PX11-PadK7)") (class "Default")
      (node (ref "U400") (pin "K7") (pinfunction "PA14_/_PX11_K7") (pintype "bidirectional+no_connect"))
    )
    (net (code "81") (name "unconnected-(U400-PA15_{slash}_PX45-PadJ7)") (class "Default")
      (node (ref "U400") (pin "J7") (pinfunction "PA15_/_PX45_J7") (pintype "bidirectional+no_connect"))
    )
    (net (code "82") (name "unconnected-(U400-PA16-PadE7)") (class "Default")
      (node (ref "U400") (pin "E7") (pinfunction "PA16_E7") (pintype "bidirectional+no_connect"))
    )
    (net (code "83") (name "unconnected-(U400-PA22_{slash}_PX20-PadH6)") (class "Default")
      (node (ref "U400") (pin "H6") (pinfunction "PA22_/_PX20_H6") (pintype "bidirectional+no_connect"))
    )
    (net (code "84") (name "unconnected-(U400-PA23_{slash}_PX46-PadG6)") (class "Default")
      (node (ref "U400") (pin "G6") (pinfunction "PA23_/_PX46_G6") (pintype "bidirectional+no_connect"))
    )
    (net (code "85") (name "unconnected-(U400-PA24_{slash}_PX17-PadJ10)") (class "Default")
      (node (ref "U400") (pin "J10") (pinfunction "PA24_/_PX17_J10") (pintype "bidirectional+no_connect"))
    )
    (net (code "86") (name "unconnected-(U400-PA27-PadA2)") (class "Default")
      (node (ref "U400") (pin "A2") (pinfunction "PA27_A2") (pintype "bidirectional+no_connect"))
    )
    (net (code "87") (name "unconnected-(U400-PA30-PadA4)") (class "Default")
      (node (ref "U400") (pin "A4") (pinfunction "PA30_A4") (pintype "bidirectional+no_connect"))
    )
    (net (code "88") (name "unconnected-(U400-PA31-PadC2)") (class "Default")
      (node (ref "U400") (pin "C2") (pinfunction "PA31_C2") (pintype "bidirectional+no_connect"))
    )
    (net (code "89") (name "unconnected-(U400-PB00-PadB1)") (class "Default")
      (node (ref "U400") (pin "B1") (pinfunction "PB00_B1") (pintype "bidirectional+no_connect"))
    )
    (net (code "90") (name "unconnected-(U400-PB01-PadB2)") (class "Default")
      (node (ref "U400") (pin "B2") (pinfunction "PB01_B2") (pintype "bidirectional+no_connect"))
    )
    (net (code "91") (name "unconnected-(U400-PB03-PadC4)") (class "Default")
      (node (ref "U400") (pin "C4") (pinfunction "PB03_C4") (pintype "bidirectional+no_connect"))
    )
    (net (code "92") (name "unconnected-(U400-PB04-PadA3)") (class "Default")
      (node (ref "U400") (pin "A3") (pinfunction "PB04_A3") (pintype "bidirectional"))
    )
    (net (code "93") (name "unconnected-(U400-PB06-PadD7)") (class "Default")
      (node (ref "U400") (pin "D7") (pinfunction "PB06_D7") (pintype "bidirectional"))
    )
    (net (code "94") (name "unconnected-(U400-PB11-PadC1)") (class "Default")
      (node (ref "U400") (pin "C1") (pinfunction "PB11_C1") (pintype "bidirectional+no_connect"))
    )
    (net (code "95") (name "unconnected-(U400-PC00_{slash}_PX14-PadK5)") (class "Default")
      (node (ref "U400") (pin "K5") (pinfunction "PC00_/_PX14_K5") (pintype "bidirectional+no_connect"))
    )
    (net (code "96") (name "unconnected-(U400-PC01-PadK6)") (class "Default")
      (node (ref "U400") (pin "K6") (pinfunction "PC01_K6") (pintype "bidirectional+no_connect"))
    )
    (net (code "97") (name "unconnected-(U400-PC04-PadB7)") (class "Default")
      (node (ref "U400") (pin "B7") (pinfunction "PC04_B7") (pintype "bidirectional+no_connect"))
    )
    (net (code "98") (name "unconnected-(U400-PC05-PadA7)") (class "Default")
      (node (ref "U400") (pin "A7") (pinfunction "PC05_A7") (pintype "bidirectional+no_connect"))
    )
    (net (code "99") (name "unconnected-(U400-PX00-PadG4)") (class "Default")
      (node (ref "U400") (pin "G4") (pinfunction "PX00_G4") (pintype "bidirectional+no_connect"))
    )
    (net (code "100") (name "unconnected-(U400-PX01-PadG2)") (class "Default")
      (node (ref "U400") (pin "G2") (pinfunction "PX01_G2") (pintype "bidirectional+no_connect"))
    )
    (net (code "101") (name "unconnected-(U400-PX02-PadG3)") (class "Default")
      (node (ref "U400") (pin "G3") (pinfunction "PX02_G3") (pintype "bidirectional+no_connect"))
    )
    (net (code "102") (name "unconnected-(U400-PX03-PadJ1)") (class "Default")
      (node (ref "U400") (pin "J1") (pinfunction "PX03_J1") (pintype "bidirectional+no_connect"))
    )
    (net (code "103") (name "unconnected-(U400-PX04-PadH1)") (class "Default")
      (node (ref "U400") (pin "H1") (pinfunction "PX04_H1") (pintype "bidirectional+no_connect"))
    )
    (net (code "104") (name "unconnected-(U400-PX05-PadG1)") (class "Default")
      (node (ref "U400") (pin "G1") (pinfunction "PX05_G1") (pintype "bidirectional+no_connect"))
    )
    (net (code "105") (name "unconnected-(U400-PX06-PadF3)") (class "Default")
      (node (ref "U400") (pin "F3") (pinfunction "PX06_F3") (pintype "bidirectional+no_connect"))
    )
    (net (code "106") (name "unconnected-(U400-PX07-PadF4)") (class "Default")
      (node (ref "U400") (pin "F4") (pinfunction "PX07_F4") (pintype "bidirectional+no_connect"))
    )
    (net (code "107") (name "unconnected-(U400-PX08-PadE3)") (class "Default")
      (node (ref "U400") (pin "E3") (pinfunction "PX08_E3") (pintype "bidirectional+no_connect"))
    )
    (net (code "108") (name "unconnected-(U400-PX09-PadE4)") (class "Default")
      (node (ref "U400") (pin "E4") (pinfunction "PX09_E4") (pintype "bidirectional+no_connect"))
    )
    (net (code "109") (name "unconnected-(U400-PX10-PadD2)") (class "Default")
      (node (ref "U400") (pin "D2") (pinfunction "PX10_D2") (pintype "bidirectional+no_connect"))
    )
    (net (code "110") (name "unconnected-(U400-PX12-PadD1)") (class "Default")
      (node (ref "U400") (pin "D1") (pinfunction "PX12_D1") (pintype "bidirectional+no_connect"))
    )
    (net (code "111") (name "unconnected-(U400-PX16_{slash}_PX53-PadD4)") (class "Default")
      (node (ref "U400") (pin "D4") (pinfunction "PX16_/_PX53_D4") (pintype "bidirectional+no_connect"))
    )
    (net (code "112") (name "unconnected-(U400-PX23-PadK1)") (class "Default")
      (node (ref "U400") (pin "K1") (pinfunction "PX23_K1") (pintype "bidirectional+no_connect"))
    )
    (net (code "113") (name "unconnected-(U400-PX24-PadJ2)") (class "Default")
      (node (ref "U400") (pin "J2") (pinfunction "PX24_J2") (pintype "bidirectional+no_connect"))
    )
    (net (code "114") (name "unconnected-(U400-PX25-PadH4)") (class "Default")
      (node (ref "U400") (pin "H4") (pinfunction "PX25_H4") (pintype "bidirectional+no_connect"))
    )
    (net (code "115") (name "unconnected-(U400-PX26-PadJ3)") (class "Default")
      (node (ref "U400") (pin "J3") (pinfunction "PX26_J3") (pintype "bidirectional+no_connect"))
    )
    (net (code "116") (name "unconnected-(U400-PX31-PadH5)") (class "Default")
      (node (ref "U400") (pin "H5") (pinfunction "PX31_H5") (pintype "bidirectional+no_connect"))
    )
    (net (code "117") (name "unconnected-(XC400-Pad2)") (class "Default")
      (node (ref "XC400") (pin "2") (pinfunction "2_2") (pintype "passive+no_connect"))
    )
    (net (code "118") (name "unconnected-(XC400-Pad4)") (class "Default")
      (node (ref "XC400") (pin "4") (pinfunction "4_4") (pintype "passive+no_connect"))
    )
  )
)
